# Sheet4.net
KiCad netlist of a schematic drawn in Altium Designer
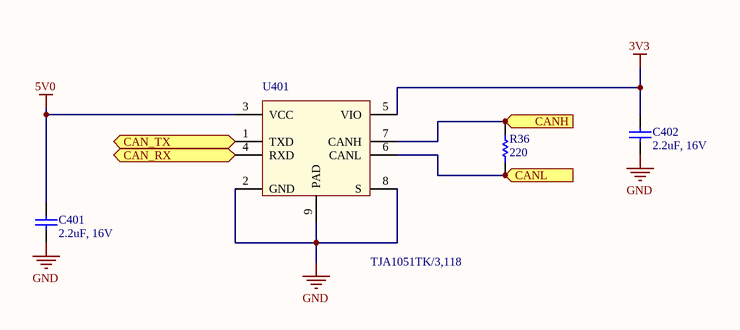
[diagram p0: Sheet4.SchDoc]

(export (version "E")
  (design (tool "Eeschema 10.0.6"))
  (components
    (comp (ref "C401")
      (value "2.2uF, 16V")
      (footprint "SMD-0603 Capacitor")
      (description "CAP 2.2u, 16V, 0603")
      (fields
        (field (name "MANUFACTURER PART NUMBER") "C1608X5R1C225M")
        (field (name "MANUFACTURER") "TDK Corporation")
      )
      (libsource (lib "Master Data Link") (part "CAP"))
    )
    (comp (ref "C402")
      (value "2.2uF, 16V")
      (footprint "SMD-0603 Capacitor")
      (description "CAP 2.2u, 16V, 0603")
      (fields
        (field (name "MANUFACTURER PART NUMBER") "C1608X5R1C225M")
        (field (name "MANUFACTURER") "TDK Corporation")
      )
      (libsource (lib "Master Data Link") (part "CAP"))
    )
    (comp (ref "R36")
      (value "220")
      (footprint "SMD-0603 Resistor")
      (description "RES SMD 220 OHM 1% 1/10W 0603")
      (fields
        (field (name "MANUFACTURER PART NUMBER") "ERJ-3EKF2200V")
        (field (name "MANUFACTURER") "Panasonic Electronic Components")
      )
      (libsource (lib "Master Data Link") (part "RES"))
    )
    (comp (ref "U401")
      (value "CAN_TRANS_1")
      (footprint "HVSON8")
      (description "IC CAN TRANSEIVER HS 8HVSON")
      (fields
        (field (name "MANUFACTURER PART NUMBER") "TJA1051TK/3,118")
        (field (name "MANUFACTURER") "NXP USA Inc.")
      )
      (libsource (lib "Master Data Link") (part "CAN_TRANS_1"))
    )
  )
  (nets
    (net (code "1") (name "/CANH") (class "Default")
      (node (ref "R36") (pin "2") (pinfunction "2_2") (pintype "passive"))
      (node (ref "U401") (pin "7") (pinfunction "CANH_7") (pintype "passive"))
    )
    (net (code "2") (name "/CANL") (class "Default")
      (node (ref "R36") (pin "1") (pinfunction "1_1") (pintype "passive"))
      (node (ref "U401") (pin "6") (pinfunction "CANL_6") (pintype "passive"))
    )
    (net (code "3") (name "/CAN_RX") (class "Default")
      (node (ref "U401") (pin "4") (pinfunction "RXD_4") (pintype "passive"))
    )
    (net (code "4") (name "/CAN_TX") (class "Default")
      (node (ref "U401") (pin "1") (pinfunction "TXD_1") (pintype "passive"))
    )
    (net (code "5") (name "3V3") (class "Default")
      (node (ref "C402") (pin "2") (pinfunction "2_2") (pintype "passive"))
      (node (ref "U401") (pin "5") (pinfunction "VIO_5") (pintype "passive"))
    )
    (net (code "6") (name "5V0") (class "Default")
      (node (ref "C401") (pin "2") (pinfunction "2_2") (pintype "passive"))
      (node (ref "U401") (pin "3") (pinfunction "VCC_3") (pintype "passive"))
    )
    (net (code "7") (name "GND") (class "Default")
      (node (ref "C401") (pin "1") (pinfunction "1_1") (pintype "passive"))
      (node (ref "C402") (pin "1") (pinfunction "1_1") (pintype "passive"))
      (node (ref "U401") (pin "2") (pinfunction "GND_2") (pintype "passive"))
      (node (ref "U401") (pin "8") (pinfunction "S_8") (pintype "passive"))
      (node (ref "U401") (pin "9") (pinfunction "PAD_9") (pintype "passive"))
    )
  )
)
